# 8-8CONRTOL.net
KiCad netlist of a schematic drawn in Altium Designer
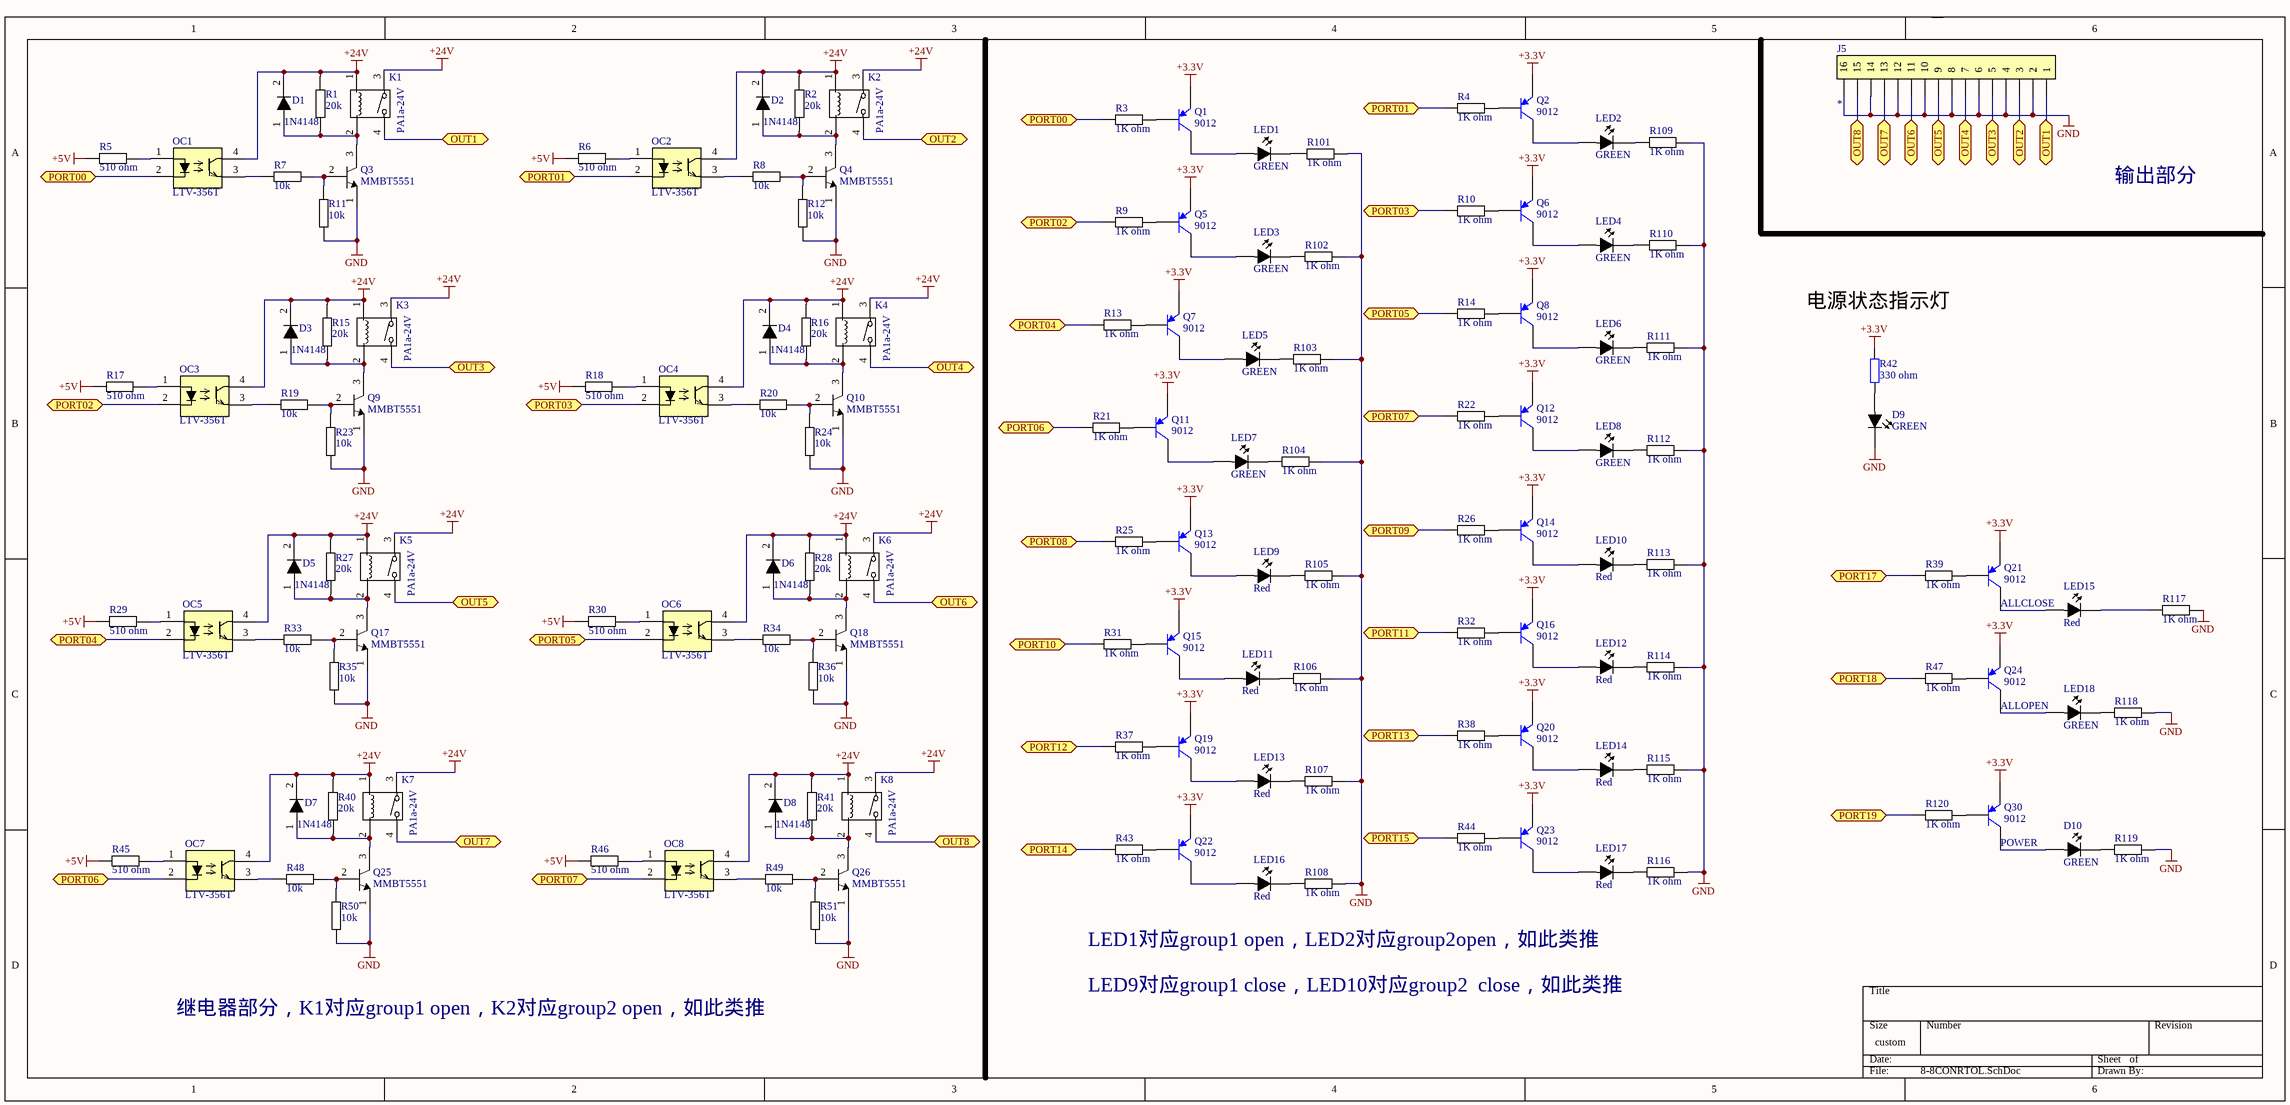
[diagram p0: 8-8CONRTOL.SchDoc]

(export (version "E")
  (design (tool "Eeschema 10.0.6"))
  (components
    (comp (ref "D1")
      (value "1N4148")
      (footprint "D 1N4148(SOD-80/LL-34)")
      (libsource (lib "mylib") (part "Diode"))
    )
    (comp (ref "D2")
      (value "1N4148")
      (footprint "D 1N4148(SOD-80/LL-34)")
      (libsource (lib "mylib") (part "Diode"))
    )
    (comp (ref "D3")
      (value "1N4148")
      (footprint "D 1N4148(SOD-80/LL-34)")
      (libsource (lib "mylib") (part "Diode"))
    )
    (comp (ref "D4")
      (value "1N4148")
      (footprint "D 1N4148(SOD-80/LL-34)")
      (libsource (lib "mylib") (part "Diode"))
    )
    (comp (ref "D5")
      (value "1N4148")
      (footprint "D 1N4148(SOD-80/LL-34)")
      (libsource (lib "mylib") (part "Diode"))
    )
    (comp (ref "D6")
      (value "1N4148")
      (footprint "D 1N4148(SOD-80/LL-34)")
      (libsource (lib "mylib") (part "Diode"))
    )
    (comp (ref "D7")
      (value "1N4148")
      (footprint "D 1N4148(SOD-80/LL-34)")
      (libsource (lib "mylib") (part "Diode"))
    )
    (comp (ref "D8")
      (value "1N4148")
      (footprint "D 1N4148(SOD-80/LL-34)")
      (libsource (lib "mylib") (part "Diode"))
    )
    (comp (ref "D9") (value "GREEN") (footprint "0805 D") (libsource (lib "mylib") (part "LED")))
    (comp (ref "D10") (value "GREEN") (footprint "LED 3mm SIP") (libsource (lib "mylib") (part "LED")))
    (comp (ref "J5")
      (value "Header 1*16")
      (footprint "8-8控制板:TIMECON5.1MMA")
      (fields (field (name "PIN") "*"))
      (libsource (lib "mylib") (part "Header 1*16"))
    )
    (comp (ref "K1") (value "PA1a-24V") (footprint "Relay PA1a-24V") (libsource (lib "mylib") (part "Relay")))
    (comp (ref "K2") (value "PA1a-24V") (footprint "Relay PA1a-24V") (libsource (lib "mylib") (part "Relay")))
    (comp (ref "K3") (value "PA1a-24V") (footprint "Relay PA1a-24V") (libsource (lib "mylib") (part "Relay")))
    (comp (ref "K4") (value "PA1a-24V") (footprint "Relay PA1a-24V") (libsource (lib "mylib") (part "Relay")))
    (comp (ref "K5") (value "PA1a-24V") (footprint "Relay PA1a-24V") (libsource (lib "mylib") (part "Relay")))
    (comp (ref "K6") (value "PA1a-24V") (footprint "Relay PA1a-24V") (libsource (lib "mylib") (part "Relay")))
    (comp (ref "K7") (value "PA1a-24V") (footprint "Relay PA1a-24V") (libsource (lib "mylib") (part "Relay")))
    (comp (ref "K8") (value "PA1a-24V") (footprint "Relay PA1a-24V") (libsource (lib "mylib") (part "Relay")))
    (comp (ref "LED1") (value "GREEN") (footprint "LED 3mm SIP") (libsource (lib "mylib") (part "LED")))
    (comp (ref "LED2") (value "GREEN") (footprint "LED 3mm SIP") (libsource (lib "mylib") (part "LED")))
    (comp (ref "LED3") (value "GREEN") (footprint "LED 3mm SIP") (libsource (lib "mylib") (part "LED")))
    (comp (ref "LED4") (value "GREEN") (footprint "LED 3mm SIP") (libsource (lib "mylib") (part "LED")))
    (comp (ref "LED5") (value "GREEN") (footprint "LED 3mm SIP") (libsource (lib "mylib") (part "LED")))
    (comp (ref "LED6") (value "GREEN") (footprint "LED 3mm SIP") (libsource (lib "mylib") (part "LED")))
    (comp (ref "LED7") (value "GREEN") (footprint "LED 3mm SIP") (libsource (lib "mylib") (part "LED")))
    (comp (ref "LED8") (value "GREEN") (footprint "LED 3mm SIP") (libsource (lib "mylib") (part "LED")))
    (comp (ref "LED9") (value "Red") (footprint "LED 3mm SIP") (libsource (lib "mylib") (part "LED")))
    (comp (ref "LED10") (value "Red") (footprint "LED 3mm SIP") (libsource (lib "mylib") (part "LED")))
    (comp (ref "LED11") (value "Red") (footprint "LED 3mm SIP") (libsource (lib "mylib") (part "LED")))
    (comp (ref "LED12") (value "Red") (footprint "LED 3mm SIP") (libsource (lib "mylib") (part "LED")))
    (comp (ref "LED13") (value "Red") (footprint "LED 3mm SIP") (libsource (lib "mylib") (part "LED")))
    (comp (ref "LED14") (value "Red") (footprint "LED 3mm SIP") (libsource (lib "mylib") (part "LED")))
    (comp (ref "LED15") (value "Red") (footprint "LED 3mm SIP") (libsource (lib "mylib") (part "LED")))
    (comp (ref "LED16") (value "Red") (footprint "LED 3mm SIP") (libsource (lib "mylib") (part "LED")))
    (comp (ref "LED17") (value "Red") (footprint "LED 3mm SIP") (libsource (lib "mylib") (part "LED")))
    (comp (ref "LED18") (value "GREEN") (footprint "LED 3mm SIP") (libsource (lib "mylib") (part "LED")))
    (comp (ref "OC1") (value "LTV-356T") (footprint "SOP-4 LTV356T") (libsource (lib "mylib") (part "Opto1")))
    (comp (ref "OC2") (value "LTV-356T") (footprint "SOP-4 LTV356T") (libsource (lib "mylib") (part "Opto1")))
    (comp (ref "OC3") (value "LTV-356T") (footprint "SOP-4 LTV356T") (libsource (lib "mylib") (part "Opto1")))
    (comp (ref "OC4") (value "LTV-356T") (footprint "SOP-4 LTV356T") (libsource (lib "mylib") (part "Opto1")))
    (comp (ref "OC5") (value "LTV-356T") (footprint "SOP-4 LTV356T") (libsource (lib "mylib") (part "Opto1")))
    (comp (ref "OC6") (value "LTV-356T") (footprint "SOP-4 LTV356T") (libsource (lib "mylib") (part "Opto1")))
    (comp (ref "OC7") (value "LTV-356T") (footprint "SOP-4 LTV356T") (libsource (lib "mylib") (part "Opto1")))
    (comp (ref "OC8") (value "LTV-356T") (footprint "SOP-4 LTV356T") (libsource (lib "mylib") (part "Opto1")))
    (comp (ref "Q1")
      (value "9012")
      (footprint "9012  SOT-23/TO-236)")
      (description "PNP Bipolar Transistor")
      (fields (field (name "PUBLISHER") "Altium Limited"))
      (libsource (lib "Miscellaneous Devices") (part "PNP"))
    )
    (comp (ref "Q2")
      (value "9012")
      (footprint "9012  SOT-23/TO-236)")
      (description "PNP Bipolar Transistor")
      (fields (field (name "PUBLISHER") "Altium Limited"))
      (libsource (lib "Miscellaneous Devices") (part "PNP"))
    )
    (comp (ref "Q3")
      (value "MMBT5551")
      (footprint "MMBT5551(SOT-23/TO-236)")
      (libsource (lib "mylib") (part "NPN"))
    )
    (comp (ref "Q4")
      (value "MMBT5551")
      (footprint "MMBT5551(SOT-23/TO-236)")
      (libsource (lib "mylib") (part "NPN"))
    )
    (comp (ref "Q5")
      (value "9012")
      (footprint "9012  SOT-23/TO-236)")
      (description "PNP Bipolar Transistor")
      (fields (field (name "PUBLISHER") "Altium Limited"))
      (libsource (lib "Miscellaneous Devices") (part "PNP"))
    )
    (comp (ref "Q6")
      (value "9012")
      (footprint "9012  SOT-23/TO-236)")
      (description "PNP Bipolar Transistor")
      (fields (field (name "PUBLISHER") "Altium Limited"))
      (libsource (lib "Miscellaneous Devices") (part "PNP"))
    )
    (comp (ref "Q7")
      (value "9012")
      (footprint "9012  SOT-23/TO-236)")
      (description "PNP Bipolar Transistor")
      (fields (field (name "PUBLISHER") "Altium Limited"))
      (libsource (lib "Miscellaneous Devices") (part "PNP"))
    )
    (comp (ref "Q8")
      (value "9012")
      (footprint "9012  SOT-23/TO-236)")
      (description "PNP Bipolar Transistor")
      (fields (field (name "PUBLISHER") "Altium Limited"))
      (libsource (lib "Miscellaneous Devices") (part "PNP"))
    )
    (comp (ref "Q9")
      (value "MMBT5551")
      (footprint "MMBT5551(SOT-23/TO-236)")
      (libsource (lib "mylib") (part "NPN"))
    )
    (comp (ref "Q10")
      (value "MMBT5551")
      (footprint "MMBT5551(SOT-23/TO-236)")
      (libsource (lib "mylib") (part "NPN"))
    )
    (comp (ref "Q11")
      (value "9012")
      (footprint "9012  SOT-23/TO-236)")
      (description "PNP Bipolar Transistor")
      (fields (field (name "PUBLISHER") "Altium Limited"))
      (libsource (lib "Miscellaneous Devices") (part "PNP"))
    )
    (comp (ref "Q12")
      (value "9012")
      (footprint "9012  SOT-23/TO-236)")
      (description "PNP Bipolar Transistor")
      (fields (field (name "PUBLISHER") "Altium Limited"))
      (libsource (lib "Miscellaneous Devices") (part "PNP"))
    )
    (comp (ref "Q13")
      (value "9012")
      (footprint "9012  SOT-23/TO-236)")
      (description "PNP Bipolar Transistor")
      (fields (field (name "PUBLISHER") "Altium Limited"))
      (libsource (lib "Miscellaneous Devices") (part "PNP"))
    )
    (comp (ref "Q14")
      (value "9012")
      (footprint "9012  SOT-23/TO-236)")
      (description "PNP Bipolar Transistor")
      (fields (field (name "PUBLISHER") "Altium Limited"))
      (libsource (lib "Miscellaneous Devices") (part "PNP"))
    )
    (comp (ref "Q15")
      (value "9012")
      (footprint "9012  SOT-23/TO-236)")
      (description "PNP Bipolar Transistor")
      (fields (field (name "PUBLISHER") "Altium Limited"))
      (libsource (lib "Miscellaneous Devices") (part "PNP"))
    )
    (comp (ref "Q16")
      (value "9012")
      (footprint "9012  SOT-23/TO-236)")
      (description "PNP Bipolar Transistor")
      (fields (field (name "PUBLISHER") "Altium Limited"))
      (libsource (lib "Miscellaneous Devices") (part "PNP"))
    )
    (comp (ref "Q17")
      (value "MMBT5551")
      (footprint "MMBT5551(SOT-23/TO-236)")
      (libsource (lib "mylib") (part "NPN"))
    )
    (comp (ref "Q18")
      (value "MMBT5551")
      (footprint "MMBT5551(SOT-23/TO-236)")
      (libsource (lib "mylib") (part "NPN"))
    )
    (comp (ref "Q19")
      (value "9012")
      (footprint "9012  SOT-23/TO-236)")
      (description "PNP Bipolar Transistor")
      (fields (field (name "PUBLISHER") "Altium Limited"))
      (libsource (lib "Miscellaneous Devices") (part "PNP"))
    )
    (comp (ref "Q20")
      (value "9012")
      (footprint "9012  SOT-23/TO-236)")
      (description "PNP Bipolar Transistor")
      (fields (field (name "PUBLISHER") "Altium Limited"))
      (libsource (lib "Miscellaneous Devices") (part "PNP"))
    )
    (comp (ref "Q21")
      (value "9012")
      (footprint "9012  SOT-23/TO-236)")
      (description "PNP Bipolar Transistor")
      (fields (field (name "PUBLISHER") "Altium Limited"))
      (libsource (lib "Miscellaneous Devices") (part "PNP"))
    )
    (comp (ref "Q22")
      (value "9012")
      (footprint "9012  SOT-23/TO-236)")
      (description "PNP Bipolar Transistor")
      (fields (field (name "PUBLISHER") "Altium Limited"))
      (libsource (lib "Miscellaneous Devices") (part "PNP"))
    )
    (comp (ref "Q23")
      (value "9012")
      (footprint "9012  SOT-23/TO-236)")
      (description "PNP Bipolar Transistor")
      (fields (field (name "PUBLISHER") "Altium Limited"))
      (libsource (lib "Miscellaneous Devices") (part "PNP"))
    )
    (comp (ref "Q24")
      (value "9012")
      (footprint "9012  SOT-23/TO-236)")
      (description "PNP Bipolar Transistor")
      (fields (field (name "PUBLISHER") "Altium Limited"))
      (libsource (lib "Miscellaneous Devices") (part "PNP"))
    )
    (comp (ref "Q25")
      (value "MMBT5551")
      (footprint "MMBT5551(SOT-23/TO-236)")
      (libsource (lib "mylib") (part "NPN"))
    )
    (comp (ref "Q26")
      (value "MMBT5551")
      (footprint "MMBT5551(SOT-23/TO-236)")
      (libsource (lib "mylib") (part "NPN"))
    )
    (comp (ref "Q30")
      (value "9012")
      (footprint "9012  SOT-23/TO-236)")
      (description "PNP Bipolar Transistor")
      (fields (field (name "PUBLISHER") "Altium Limited"))
      (libsource (lib "Miscellaneous Devices") (part "PNP"))
    )
    (comp (ref "R1")
      (value "20k")
      (footprint "0805 R 1/8W")
      (fields (field (name "Comment") "RES"))
      (libsource (lib "") (part "RES_1"))
    )
    (comp (ref "R2")
      (value "20k")
      (footprint "0805 R 1/8W")
      (fields (field (name "Comment") "RES"))
      (libsource (lib "") (part "RES_1"))
    )
    (comp (ref "R3")
      (value "1K ohm")
      (footprint "0805 R 1/8W")
      (fields (field (name "Comment") "RES"))
      (libsource (lib "mylib") (part "RES"))
    )
    (comp (ref "R4")
      (value "1K ohm")
      (footprint "0805 R 1/8W")
      (fields (field (name "Comment") "RES"))
      (libsource (lib "mylib") (part "RES"))
    )
    (comp (ref "R5")
      (value "510 ohm")
      (footprint "0805 R 1/8W")
      (fields (field (name "Comment") "RES"))
      (libsource (lib "mylib") (part "RES"))
    )
    (comp (ref "R6")
      (value "510 ohm")
      (footprint "0805 R 1/8W")
      (fields (field (name "Comment") "RES"))
      (libsource (lib "mylib") (part "RES"))
    )
    (comp (ref "R7")
      (value "10k")
      (footprint "0805 R 1/8W")
      (fields (field (name "Comment") "RES"))
      (libsource (lib "mylib") (part "RES"))
    )
    (comp (ref "R8")
      (value "10k")
      (footprint "0805 R 1/8W")
      (fields (field (name "Comment") "RES"))
      (libsource (lib "mylib") (part "RES"))
    )
    (comp (ref "R9")
      (value "1K ohm")
      (footprint "0805 R 1/8W")
      (fields (field (name "Comment") "RES"))
      (libsource (lib "mylib") (part "RES"))
    )
    (comp (ref "R10")
      (value "1K ohm")
      (footprint "0805 R 1/8W")
      (fields (field (name "Comment") "RES"))
      (libsource (lib "mylib") (part "RES"))
    )
    (comp (ref "R11")
      (value "10k")
      (footprint "0805 R 1/8W")
      (fields (field (name "Comment") "RES"))
      (libsource (lib "") (part "RES_1"))
    )
    (comp (ref "R12")
      (value "10k")
      (footprint "0805 R 1/8W")
      (fields (field (name "Comment") "RES"))
      (libsource (lib "") (part "RES_1"))
    )
    (comp (ref "R13")
      (value "1K ohm")
      (footprint "0805 R 1/8W")
      (fields (field (name "Comment") "RES"))
      (libsource (lib "mylib") (part "RES"))
    )
    (comp (ref "R14")
      (value "1K ohm")
      (footprint "0805 R 1/8W")
      (fields (field (name "Comment") "RES"))
      (libsource (lib "mylib") (part "RES"))
    )
    (comp (ref "R15")
      (value "20k")
      (footprint "0805 R 1/8W")
      (fields (field (name "Comment") "RES"))
      (libsource (lib "") (part "RES_1"))
    )
    (comp (ref "R16")
      (value "20k")
      (footprint "0805 R 1/8W")
      (fields (field (name "Comment") "RES"))
      (libsource (lib "") (part "RES_1"))
    )
    (comp (ref "R17")
      (value "510 ohm")
      (footprint "0805 R 1/8W")
      (fields (field (name "Comment") "RES"))
      (libsource (lib "mylib") (part "RES"))
    )
    (comp (ref "R18")
      (value "510 ohm")
      (footprint "0805 R 1/8W")
      (fields (field (name "Comment") "RES"))
      (libsource (lib "mylib") (part "RES"))
    )
    (comp (ref "R19")
      (value "10k")
      (footprint "0805 R 1/8W")
      (fields (field (name "Comment") "RES"))
      (libsource (lib "mylib") (part "RES"))
    )
    (comp (ref "R20")
      (value "10k")
      (footprint "0805 R 1/8W")
      (fields (field (name "Comment") "RES"))
      (libsource (lib "mylib") (part "RES"))
    )
    (comp (ref "R21")
      (value "1K ohm")
      (footprint "0805 R 1/8W")
      (fields (field (name "Comment") "RES"))
      (libsource (lib "mylib") (part "RES"))
    )
    (comp (ref "R22")
      (value "1K ohm")
      (footprint "0805 R 1/8W")
      (fields (field (name "Comment") "RES"))
      (libsource (lib "mylib") (part "RES"))
    )
    (comp (ref "R23")
      (value "10k")
      (footprint "0805 R 1/8W")
      (fields (field (name "Comment") "RES"))
      (libsource (lib "") (part "RES_1"))
    )
    (comp (ref "R24")
      (value "10k")
      (footprint "0805 R 1/8W")
      (fields (field (name "Comment") "RES"))
      (libsource (lib "") (part "RES_1"))
    )
    (comp (ref "R25")
      (value "1K ohm")
      (footprint "0805 R 1/8W")
      (fields (field (name "Comment") "RES"))
      (libsource (lib "mylib") (part "RES"))
    )
    (comp (ref "R26")
      (value "1K ohm")
      (footprint "0805 R 1/8W")
      (fields (field (name "Comment") "RES"))
      (libsource (lib "mylib") (part "RES"))
    )
    (comp (ref "R27")
      (value "20k")
      (footprint "0805 R 1/8W")
      (fields (field (name "Comment") "RES"))
      (libsource (lib "") (part "RES_1"))
    )
    (comp (ref "R28")
      (value "20k")
      (footprint "0805 R 1/8W")
      (fields (field (name "Comment") "RES"))
      (libsource (lib "") (part "RES_1"))
    )
    (comp (ref "R29")
      (value "510 ohm")
      (footprint "0805 R 1/8W")
      (fields (field (name "Comment") "RES"))
      (libsource (lib "mylib") (part "RES"))
    )
    (comp (ref "R30")
      (value "510 ohm")
      (footprint "0805 R 1/8W")
      (fields (field (name "Comment") "RES"))
      (libsource (lib "mylib") (part "RES"))
    )
    (comp (ref "R31")
      (value "1K ohm")
      (footprint "0805 R 1/8W")
      (fields (field (name "Comment") "RES"))
      (libsource (lib "mylib") (part "RES"))
    )
    (comp (ref "R32")
      (value "1K ohm")
      (footprint "0805 R 1/8W")
      (fields (field (name "Comment") "RES"))
      (libsource (lib "mylib") (part "RES"))
    )
    (comp (ref "R33")
      (value "10k")
      (footprint "0805 R 1/8W")
      (fields (field (name "Comment") "RES"))
      (libsource (lib "mylib") (part "RES"))
    )
    (comp (ref "R34")
      (value "10k")
      (footprint "0805 R 1/8W")
      (fields (field (name "Comment") "RES"))
      (libsource (lib "mylib") (part "RES"))
    )
    (comp (ref "R35")
      (value "10k")
      (footprint "0805 R 1/8W")
      (fields (field (name "Comment") "RES"))
      (libsource (lib "") (part "RES_1"))
    )
    (comp (ref "R36")
      (value "10k")
      (footprint "0805 R 1/8W")
      (fields (field (name "Comment") "RES"))
      (libsource (lib "") (part "RES_1"))
    )
    (comp (ref "R37")
      (value "1K ohm")
      (footprint "0805 R 1/8W")
      (fields (field (name "Comment") "RES"))
      (libsource (lib "mylib") (part "RES"))
    )
    (comp (ref "R38")
      (value "1K ohm")
      (footprint "0805 R 1/8W")
      (fields (field (name "Comment") "RES"))
      (libsource (lib "mylib") (part "RES"))
    )
    (comp (ref "R39")
      (value "1K ohm")
      (footprint "0805 R 1/8W")
      (fields (field (name "Comment") "RES"))
      (libsource (lib "mylib") (part "RES"))
    )
    (comp (ref "R40")
      (value "20k")
      (footprint "0805 R 1/8W")
      (fields (field (name "Comment") "RES"))
      (libsource (lib "") (part "RES_1"))
    )
    (comp (ref "R41")
      (value "20k")
      (footprint "0805 R 1/8W")
      (fields (field (name "Comment") "RES"))
      (libsource (lib "") (part "RES_1"))
    )
    (comp (ref "R42")
      (value "330 ohm")
      (footprint "0805 D")
      (description "Resistor")
      (fields (field (name "PUBLISHER") "Altium Limited"))
      (libsource (lib "ABIDO") (part "Res2"))
    )
    (comp (ref "R43")
      (value "1K ohm")
      (footprint "0805 R 1/8W")
      (fields (field (name "Comment") "RES"))
      (libsource (lib "mylib") (part "RES"))
    )
    (comp (ref "R44")
      (value "1K ohm")
      (footprint "0805 R 1/8W")
      (fields (field (name "Comment") "RES"))
      (libsource (lib "mylib") (part "RES"))
    )
    (comp (ref "R45")
      (value "510 ohm")
      (footprint "0805 R 1/8W")
      (fields (field (name "Comment") "RES"))
      (libsource (lib "mylib") (part "RES"))
    )
    (comp (ref "R46")
      (value "510 ohm")
      (footprint "0805 R 1/8W")
      (fields (field (name "Comment") "RES"))
      (libsource (lib "mylib") (part "RES"))
    )
    (comp (ref "R47")
      (value "1K ohm")
      (footprint "0805 R 1/8W")
      (fields (field (name "Comment") "RES"))
      (libsource (lib "mylib") (part "RES"))
    )
    (comp (ref "R48")
      (value "10k")
      (footprint "0805 R 1/8W")
      (fields (field (name "Comment") "RES"))
      (libsource (lib "mylib") (part "RES"))
    )
    (comp (ref "R49")
      (value "10k")
      (footprint "0805 R 1/8W")
      (fields (field (name "Comment") "RES"))
      (libsource (lib "mylib") (part "RES"))
    )
    (comp (ref "R50")
      (value "10k")
      (footprint "0805 R 1/8W")
      (fields (field (name "Comment") "RES"))
      (libsource (lib "") (part "RES_1"))
    )
    (comp (ref "R51")
      (value "10k")
      (footprint "0805 R 1/8W")
      (fields (field (name "Comment") "RES"))
      (libsource (lib "") (part "RES_1"))
    )
    (comp (ref "R101")
      (value "1K ohm")
      (footprint "0805 R 1/8W")
      (fields (field (name "Comment") "RES"))
      (libsource (lib "mylib") (part "RES"))
    )
    (comp (ref "R102")
      (value "1K ohm")
      (footprint "0805 R 1/8W")
      (fields (field (name "Comment") "RES"))
      (libsource (lib "mylib") (part "RES"))
    )
    (comp (ref "R103")
      (value "1K ohm")
      (footprint "0805 R 1/8W")
      (fields (field (name "Comment") "RES"))
      (libsource (lib "mylib") (part "RES"))
    )
    (comp (ref "R104")
      (value "1K ohm")
      (footprint "0805 R 1/8W")
      (fields (field (name "Comment") "RES"))
      (libsource (lib "mylib") (part "RES"))
    )
    (comp (ref "R105")
      (value "1K ohm")
      (footprint "0805 R 1/8W")
      (fields (field (name "Comment") "RES"))
      (libsource (lib "mylib") (part "RES"))
    )
    (comp (ref "R106")
      (value "1K ohm")
      (footprint "0805 R 1/8W")
      (fields (field (name "Comment") "RES"))
      (libsource (lib "mylib") (part "RES"))
    )
    (comp (ref "R107")
      (value "1K ohm")
      (footprint "0805 R 1/8W")
      (fields (field (name "Comment") "RES"))
      (libsource (lib "mylib") (part "RES"))
    )
    (comp (ref "R108")
      (value "1K ohm")
      (footprint "0805 R 1/8W")
      (fields (field (name "Comment") "RES"))
      (libsource (lib "mylib") (part "RES"))
    )
    (comp (ref "R109")
      (value "1K ohm")
      (footprint "0805 R 1/8W")
      (fields (field (name "Comment") "RES"))
      (libsource (lib "mylib") (part "RES"))
    )
    (comp (ref "R110")
      (value "1K ohm")
      (footprint "0805 R 1/8W")
      (fields (field (name "Comment") "RES"))
      (libsource (lib "mylib") (part "RES"))
    )
    (comp (ref "R111")
      (value "1K ohm")
      (footprint "0805 R 1/8W")
      (fields (field (name "Comment") "RES"))
      (libsource (lib "mylib") (part "RES"))
    )
    (comp (ref "R112")
      (value "1K ohm")
      (footprint "0805 R 1/8W")
      (fields (field (name "Comment") "RES"))
      (libsource (lib "mylib") (part "RES"))
    )
    (comp (ref "R113")
      (value "1K ohm")
      (footprint "0805 R 1/8W")
      (fields (field (name "Comment") "RES"))
      (libsource (lib "mylib") (part "RES"))
    )
    (comp (ref "R114")
      (value "1K ohm")
      (footprint "0805 R 1/8W")
      (fields (field (name "Comment") "RES"))
      (libsource (lib "mylib") (part "RES"))
    )
    (comp (ref "R115")
      (value "1K ohm")
      (footprint "0805 R 1/8W")
      (fields (field (name "Comment") "RES"))
      (libsource (lib "mylib") (part "RES"))
    )
    (comp (ref "R116")
      (value "1K ohm")
      (footprint "0805 R 1/8W")
      (fields (field (name "Comment") "RES"))
      (libsource (lib "mylib") (part "RES"))
    )
    (comp (ref "R117")
      (value "1K ohm")
      (footprint "0805 R 1/8W")
      (fields (field (name "Comment") "RES"))
      (libsource (lib "mylib") (part "RES"))
    )
    (comp (ref "R118")
      (value "1K ohm")
      (footprint "0805 R 1/8W")
      (fields (field (name "Comment") "RES"))
      (libsource (lib "mylib") (part "RES"))
    )
    (comp (ref "R119")
      (value "1K ohm")
      (footprint "0805 R 1/8W")
      (fields (field (name "Comment") "RES"))
      (libsource (lib "mylib") (part "RES"))
    )
    (comp (ref "R120")
      (value "1K ohm")
      (footprint "0805 R 1/8W")
      (fields (field (name "Comment") "RES"))
      (libsource (lib "mylib") (part "RES"))
    )
  )
  (nets
    (net (code "1") (name "+3.3V") (class "Default")
      (node (ref "Q1") (pin "2") (pinfunction "E_2") (pintype "passive"))
      (node (ref "Q11") (pin "2") (pinfunction "E_2") (pintype "passive"))
      (node (ref "Q12") (pin "2") (pinfunction "E_2") (pintype "passive"))
      (node (ref "Q13") (pin "2") (pinfunction "E_2") (pintype "passive"))
      (node (ref "Q14") (pin "2") (pinfunction "E_2") (pintype "passive"))
      (node (ref "Q15") (pin "2") (pinfunction "E_2") (pintype "passive"))
      (node (ref "Q16") (pin "2") (pinfunction "E_2") (pintype "passive"))
      (node (ref "Q19") (pin "2") (pinfunction "E_2") (pintype "passive"))
      (node (ref "Q2") (pin "2") (pinfunction "E_2") (pintype "passive"))
      (node (ref "Q20") (pin "2") (pinfunction "E_2") (pintype "passive"))
      (node (ref "Q21") (pin "2") (pinfunction "E_2") (pintype "passive"))
      (node (ref "Q22") (pin "2") (pinfunction "E_2") (pintype "passive"))
      (node (ref "Q23") (pin "2") (pinfunction "E_2") (pintype "passive"))
      (node (ref "Q24") (pin "2") (pinfunction "E_2") (pintype "passive"))
      (node (ref "Q30") (pin "2") (pinfunction "E_2") (pintype "passive"))
      (node (ref "Q5") (pin "2") (pinfunction "E_2") (pintype "passive"))
      (node (ref "Q6") (pin "2") (pinfunction "E_2") (pintype "passive"))
      (node (ref "Q7") (pin "2") (pinfunction "E_2") (pintype "passive"))
      (node (ref "Q8") (pin "2") (pinfunction "E_2") (pintype "passive"))
      (node (ref "R42") (pin "2") (pinfunction "2_2") (pintype "passive"))
    )
    (net (code "2") (name "+5V") (class "Default")
      (node (ref "R17") (pin "1") (pinfunction "1_1") (pintype "passive"))
      (node (ref "R18") (pin "1") (pinfunction "1_1") (pintype "passive"))
      (node (ref "R29") (pin "1") (pinfunction "1_1") (pintype "passive"))
      (node (ref "R30") (pin "1") (pinfunction "1_1") (pintype "passive"))
      (node (ref "R45") (pin "1") (pinfunction "1_1") (pintype "passive"))
      (node (ref "R46") (pin "1") (pinfunction "1_1") (pintype "passive"))
      (node (ref "R5") (pin "1") (pinfunction "1_1") (pintype "passive"))
      (node (ref "R6") (pin "1") (pinfunction "1_1") (pintype "passive"))
    )
    (net (code "3") (name "+24V") (class "Default")
      (node (ref "D1") (pin "2") (pinfunction "K_2") (pintype "passive"))
      (node (ref "D2") (pin "2") (pinfunction "K_2") (pintype "passive"))
      (node (ref "D3") (pin "2") (pinfunction "K_2") (pintype "passive"))
      (node (ref "D4") (pin "2") (pinfunction "K_2") (pintype "passive"))
      (node (ref "D5") (pin "2") (pinfunction "K_2") (pintype "passive"))
      (node (ref "D6") (pin "2") (pinfunction "K_2") (pintype "passive"))
      (node (ref "D7") (pin "2") (pinfunction "K_2") (pintype "passive"))
      (node (ref "D8") (pin "2") (pinfunction "K_2") (pintype "passive"))
      (node (ref "K1") (pin "1") (pinfunction "1_1") (pintype "passive"))
      (node (ref "K1") (pin "3") (pinfunction "3_3") (pintype "passive"))
      (node (ref "K2") (pin "1") (pinfunction "1_1") (pintype "passive"))
      (node (ref "K2") (pin "3") (pinfunction "3_3") (pintype "passive"))
      (node (ref "K3") (pin "1") (pinfunction "1_1") (pintype "passive"))
      (node (ref "K3") (pin "3") (pinfunction "3_3") (pintype "passive"))
      (node (ref "K4") (pin "1") (pinfunction "1_1") (pintype "passive"))
      (node (ref "K4") (pin "3") (pinfunction "3_3") (pintype "passive"))
      (node (ref "K5") (pin "1") (pinfunction "1_1") (pintype "passive"))
      (node (ref "K5") (pin "3") (pinfunction "3_3") (pintype "passive"))
      (node (ref "K6") (pin "1") (pinfunction "1_1") (pintype "passive"))
      (node (ref "K6") (pin "3") (pinfunction "3_3") (pintype "passive"))
      (node (ref "K7") (pin "1") (pinfunction "1_1") (pintype "passive"))
      (node (ref "K7") (pin "3") (pinfunction "3_3") (pintype "passive"))
      (node (ref "K8") (pin "1") (pinfunction "1_1") (pintype "passive"))
      (node (ref "K8") (pin "3") (pinfunction "3_3") (pintype "passive"))
      (node (ref "OC1") (pin "4") (pintype "passive"))
      (node (ref "OC2") (pin "4") (pintype "passive"))
      (node (ref "OC3") (pin "4") (pintype "passive"))
      (node (ref "OC4") (pin "4") (pintype "passive"))
      (node (ref "OC5") (pin "4") (pintype "passive"))
      (node (ref "OC6") (pin "4") (pintype "passive"))
      (node (ref "OC7") (pin "4") (pintype "passive"))
      (node (ref "OC8") (pin "4") (pintype "passive"))
      (node (ref "R1") (pin "2") (pinfunction "2_2") (pintype "passive"))
      (node (ref "R15") (pin "2") (pinfunction "2_2") (pintype "passive"))
      (node (ref "R16") (pin "2") (pinfunction "2_2") (pintype "passive"))
      (node (ref "R2") (pin "2") (pinfunction "2_2") (pintype "passive"))
      (node (ref "R27") (pin "2") (pinfunction "2_2") (pintype "passive"))
      (node (ref "R28") (pin "2") (pinfunction "2_2") (pintype "passive"))
      (node (ref "R40") (pin "2") (pinfunction "2_2") (pintype "passive"))
      (node (ref "R41") (pin "2") (pinfunction "2_2") (pintype "passive"))
    )
    (net (code "4") (name "/OUT1") (class "Default")
      (node (ref "J5") (pin "1") (pinfunction "1_1") (pintype "passive"))
      (node (ref "K1") (pin "4") (pinfunction "4_4") (pintype "passive"))
    )
    (net (code "5") (name "/OUT2") (class "Default")
      (node (ref "J5") (pin "3") (pinfunction "3_3") (pintype "passive"))
      (node (ref "K2") (pin "4") (pinfunction "4_4") (pintype "passive"))
    )
    (net (code "6") (name "/OUT3") (class "Default")
      (node (ref "J5") (pin "5") (pinfunction "5_5") (pintype "passive"))
      (node (ref "K3") (pin "4") (pinfunction "4_4") (pintype "passive"))
    )
    (net (code "7") (name "/OUT4") (class "Default")
      (node (ref "J5") (pin "7") (pinfunction "7_7") (pintype "passive"))
      (node (ref "K4") (pin "4") (pinfunction "4_4") (pintype "passive"))
    )
    (net (code "8") (name "/OUT5") (class "Default")
      (node (ref "J5") (pin "9") (pinfunction "9_9") (pintype "passive"))
      (node (ref "K5") (pin "4") (pinfunction "4_4") (pintype "passive"))
    )
    (net (code "9") (name "/OUT6") (class "Default")
      (node (ref "J5") (pin "11") (pinfunction "11_11") (pintype "passive"))
      (node (ref "K6") (pin "4") (pinfunction "4_4") (pintype "passive"))
    )
    (net (code "10") (name "/OUT7") (class "Default")
      (node (ref "J5") (pin "13") (pinfunction "13_13") (pintype "passive"))
      (node (ref "K7") (pin "4") (pinfunction "4_4") (pintype "passive"))
    )
    (net (code "11") (name "/OUT8") (class "Default")
      (node (ref "J5") (pin "15") (pinfunction "15_15") (pintype "passive"))
      (node (ref "K8") (pin "4") (pinfunction "4_4") (pintype "passive"))
    )
    (net (code "12") (name "/PORT00") (class "Default")
      (node (ref "OC1") (pin "2") (pintype "passive"))
      (node (ref "R3") (pin "1") (pinfunction "1_1") (pintype "passive"))
    )
    (net (code "13") (name "/PORT01") (class "Default")
      (node (ref "OC2") (pin "2") (pintype "passive"))
      (node (ref "R4") (pin "1") (pinfunction "1_1") (pintype "passive"))
    )
    (net (code "14") (name "/PORT02") (class "Default")
      (node (ref "OC3") (pin "2") (pintype "passive"))
      (node (ref "R9") (pin "1") (pinfunction "1_1") (pintype "passive"))
    )
    (net (code "15") (name "/PORT03") (class "Default")
      (node (ref "OC4") (pin "2") (pintype "passive"))
      (node (ref "R10") (pin "1") (pinfunction "1_1") (pintype "passive"))
    )
    (net (code "16") (name "/PORT04") (class "Default")
      (node (ref "OC5") (pin "2") (pintype "passive"))
      (node (ref "R13") (pin "1") (pinfunction "1_1") (pintype "passive"))
    )
    (net (code "17") (name "/PORT05") (class "Default")
      (node (ref "OC6") (pin "2") (pintype "passive"))
      (node (ref "R14") (pin "1") (pinfunction "1_1") (pintype "passive"))
    )
    (net (code "18") (name "/PORT06") (class "Default")
      (node (ref "OC7") (pin "2") (pintype "passive"))
      (node (ref "R21") (pin "1") (pinfunction "1_1") (pintype "passive"))
    )
    (net (code "19") (name "/PORT07") (class "Default")
      (node (ref "OC8") (pin "2") (pintype "passive"))
      (node (ref "R22") (pin "1") (pinfunction "1_1") (pintype "passive"))
    )
    (net (code "20") (name "/PORT08") (class "Default")
      (node (ref "R25") (pin "1") (pinfunction "1_1") (pintype "passive"))
    )
    (net (code "21") (name "/PORT09") (class "Default")
      (node (ref "R26") (pin "1") (pinfunction "1_1") (pintype "passive"))
    )
    (net (code "22") (name "/PORT10") (class "Default")
      (node (ref "R31") (pin "1") (pinfunction "1_1") (pintype "passive"))
    )
    (net (code "23") (name "/PORT11") (class "Default")
      (node (ref "R32") (pin "1") (pinfunction "1_1") (pintype "passive"))
    )
    (net (code "24") (name "/PORT12") (class "Default")
      (node (ref "R37") (pin "1") (pinfunction "1_1") (pintype "passive"))
    )
    (net (code "25") (name "/PORT13") (class "Default")
      (node (ref "R38") (pin "1") (pinfunction "1_1") (pintype "passive"))
    )
    (net (code "26") (name "/PORT14") (class "Default")
      (node (ref "R43") (pin "1") (pinfunction "1_1") (pintype "passive"))
    )
    (net (code "27") (name "/PORT15") (class "Default")
      (node (ref "R44") (pin "1") (pinfunction "1_1") (pintype "passive"))
    )
    (net (code "28") (name "/PORT17") (class "Default")
      (node (ref "R39") (pin "1") (pinfunction "1_1") (pintype "passive"))
    )
    (net (code "29") (name "/PORT18") (class "Default")
      (node (ref "R47") (pin "1") (pinfunction "1_1") (pintype "passive"))
    )
    (net (code "30") (name "/PORT19") (class "Default")
      (node (ref "R120") (pin "1") (pinfunction "1_1") (pintype "passive"))
    )
    (net (code "31") (name "GND") (class "Default")
      (node (ref "D9") (pin "2") (pinfunction "K_2") (pintype "passive"))
      (node (ref "J5") (pin "10") (pinfunction "10_10") (pintype "passive"))
      (node (ref "J5") (pin "12") (pinfunction "12_12") (pintype "passive"))
      (node (ref "J5") (pin "14") (pinfunction "14_14") (pintype "passive"))
      (node (ref "J5") (pin "16") (pinfunction "16_16") (pintype "passive"))
      (node (ref "J5") (pin "2") (pinfunction "2_2") (pintype "passive"))
      (node (ref "J5") (pin "4") (pinfunction "4_4") (pintype "passive"))
      (node (ref "J5") (pin "6") (pinfunction "6_6") (pintype "passive"))
      (node (ref "J5") (pin "8") (pinfunction "8_8") (pintype "passive"))
      (node (ref "Q10") (pin "1") (pinfunction "E_1") (pintype "passive"))
      (node (ref "Q17") (pin "1") (pinfunction "E_1") (pintype "passive"))
      (node (ref "Q18") (pin "1") (pinfunction "E_1") (pintype "passive"))
      (node (ref "Q25") (pin "1") (pinfunction "E_1") (pintype "passive"))
      (node (ref "Q26") (pin "1") (pinfunction "E_1") (pintype "passive"))
      (node (ref "Q3") (pin "1") (pinfunction "E_1") (pintype "passive"))
      (node (ref "Q4") (pin "1") (pinfunction "E_1") (pintype "passive"))
      (node (ref "Q9") (pin "1") (pinfunction "E_1") (pintype "passive"))
      (node (ref "R101") (pin "2") (pinfunction "2_2") (pintype "passive"))
      (node (ref "R102") (pin "2") (pinfunction "2_2") (pintype "passive"))
      (node (ref "R103") (pin "2") (pinfunction "2_2") (pintype "passive"))
      (node (ref "R104") (pin "2") (pinfunction "2_2") (pintype "passive"))
      (node (ref "R105") (pin "2") (pinfunction "2_2") (pintype "passive"))
      (node (ref "R106") (pin "2") (pinfunction "2_2") (pintype "passive"))
      (node (ref "R107") (pin "2") (pinfunction "2_2") (pintype "passive"))
      (node (ref "R108") (pin "2") (pinfunction "2_2") (pintype "passive"))
      (node (ref "R109") (pin "2") (pinfunction "2_2") (pintype "passive"))
      (node (ref "R11") (pin "1") (pinfunction "1_1") (pintype "passive"))
      (node (ref "R110") (pin "2") (pinfunction "2_2") (pintype "passive"))
      (node (ref "R111") (pin "2") (pinfunction "2_2") (pintype "passive"))
      (node (ref "R112") (pin "2") (pinfunction "2_2") (pintype "passive"))
      (node (ref "R113") (pin "2") (pinfunction "2_2") (pintype "passive"))
      (node (ref "R114") (pin "2") (pinfunction "2_2") (pintype "passive"))
      (node (ref "R115") (pin "2") (pinfunction "2_2") (pintype "passive"))
      (node (ref "R116") (pin "2") (pinfunction "2_2") (pintype "passive"))
      (node (ref "R117") (pin "2") (pinfunction "2_2") (pintype "passive"))
      (node (ref "R118") (pin "2") (pinfunction "2_2") (pintype "passive"))
      (node (ref "R119") (pin "2") (pinfunction "2_2") (pintype "passive"))
      (node (ref "R12") (pin "1") (pinfunction "1_1") (pintype "passive"))
      (node (ref "R23") (pin "1") (pinfunction "1_1") (pintype "passive"))
      (node (ref "R24") (pin "1") (pinfunction "1_1") (pintype "passive"))
      (node (ref "R35") (pin "1") (pinfunction "1_1") (pintype "passive"))
      (node (ref "R36") (pin "1") (pinfunction "1_1") (pintype "passive"))
      (node (ref "R50") (pin "1") (pinfunction "1_1") (pintype "passive"))
      (node (ref "R51") (pin "1") (pinfunction "1_1") (pintype "passive"))
    )
    (net (code "32") (name "Net-(D1-A)") (class "Default")
      (node (ref "D1") (pin "1") (pinfunction "A_1") (pintype "passive"))
      (node (ref "K1") (pin "2") (pinfunction "2_2") (pintype "passive"))
      (node (ref "Q3") (pin "3") (pinfunction "C_3") (pintype "passive"))
      (node (ref "R1") (pin "1") (pinfunction "1_1") (pintype "passive"))
    )
    (net (code "33") (name "Net-(D2-A)") (class "Default")
      (node (ref "D2") (pin "1") (pinfunction "A_1") (pintype "passive"))
      (node (ref "K2") (pin "2") (pinfunction "2_2") (pintype "passive"))
      (node (ref "Q4") (pin "3") (pinfunction "C_3") (pintype "passive"))
      (node (ref "R2") (pin "1") (pinfunction "1_1") (pintype "passive"))
    )
    (net (code "34") (name "Net-(D3-A)") (class "Default")
      (node (ref "D3") (pin "1") (pinfunction "A_1") (pintype "passive"))
      (node (ref "K3") (pin "2") (pinfunction "2_2") (pintype "passive"))
      (node (ref "Q9") (pin "3") (pinfunction "C_3") (pintype "passive"))
      (node (ref "R15") (pin "1") (pinfunction "1_1") (pintype "passive"))
    )
    (net (code "35") (name "Net-(D4-A)") (class "Default")
      (node (ref "D4") (pin "1") (pinfunction "A_1") (pintype "passive"))
      (node (ref "K4") (pin "2") (pinfunction "2_2") (pintype "passive"))
      (node (ref "Q10") (pin "3") (pinfunction "C_3") (pintype "passive"))
      (node (ref "R16") (pin "1") (pinfunction "1_1") (pintype "passive"))
    )
    (net (code "36") (name "Net-(D5-A)") (class "Default")
      (node (ref "D5") (pin "1") (pinfunction "A_1") (pintype "passive"))
      (node (ref "K5") (pin "2") (pinfunction "2_2") (pintype "passive"))
      (node (ref "Q17") (pin "3") (pinfunction "C_3") (pintype "passive"))
      (node (ref "R27") (pin "1") (pinfunction "1_1") (pintype "passive"))
    )
    (net (code "37") (name "Net-(D6-A)") (class "Default")
      (node (ref "D6") (pin "1") (pinfunction "A_1") (pintype "passive"))
      (node (ref "K6") (pin "2") (pinfunction "2_2") (pintype "passive"))
      (node (ref "Q18") (pin "3") (pinfunction "C_3") (pintype "passive"))
      (node (ref "R28") (pin "1") (pinfunction "1_1") (pintype "passive"))
    )
    (net (code "38") (name "Net-(D7-A)") (class "Default")
      (node (ref "D7") (pin "1") (pinfunction "A_1") (pintype "passive"))
      (node (ref "K7") (pin "2") (pinfunction "2_2") (pintype "passive"))
      (node (ref "Q25") (pin "3") (pinfunction "C_3") (pintype "passive"))
      (node (ref "R40") (pin "1") (pinfunction "1_1") (pintype "passive"))
    )
    (net (code "39") (name "Net-(D8-A)") (class "Default")
      (node (ref "D8") (pin "1") (pinfunction "A_1") (pintype "passive"))
      (node (ref "K8") (pin "2") (pinfunction "2_2") (pintype "passive"))
      (node (ref "Q26") (pin "3") (pinfunction "C_3") (pintype "passive"))
      (node (ref "R41") (pin "1") (pinfunction "1_1") (pintype "passive"))
    )
    (net (code "40") (name "Net-(D9-A)") (class "Default")
      (node (ref "D9") (pin "1") (pinfunction "A_1") (pintype "passive"))
      (node (ref "R42") (pin "1") (pinfunction "1_1") (pintype "passive"))
    )
    (net (code "41") (name "Net-(D10-A)") (class "Default")
      (node (ref "D10") (pin "1") (pinfunction "A_1") (pintype "passive"))
      (node (ref "Q30") (pin "3") (pinfunction "C_3") (pintype "passive"))
    )
    (net (code "42") (name "Net-(D10-K)") (class "Default")
      (node (ref "D10") (pin "2") (pinfunction "K_2") (pintype "passive"))
      (node (ref "R119") (pin "1") (pinfunction "1_1") (pintype "passive"))
    )
    (net (code "43") (name "Net-(LED1-A)") (class "Default")
      (node (ref "LED1") (pin "1") (pinfunction "A_1") (pintype "passive"))
      (node (ref "Q1") (pin "3") (pinfunction "C_3") (pintype "passive"))
    )
    (net (code "44") (name "Net-(LED1-K)") (class "Default")
      (node (ref "LED1") (pin "2") (pinfunction "K_2") (pintype "passive"))
      (node (ref "R101") (pin "1") (pinfunction "1_1") (pintype "passive"))
    )
    (net (code "45") (name "Net-(LED2-A)") (class "Default")
      (node (ref "LED2") (pin "1") (pinfunction "A_1") (pintype "passive"))
      (node (ref "Q2") (pin "3") (pinfunction "C_3") (pintype "passive"))
    )
    (net (code "46") (name "Net-(LED2-K)") (class "Default")
      (node (ref "LED2") (pin "2") (pinfunction "K_2") (pintype "passive"))
      (node (ref "R109") (pin "1") (pinfunction "1_1") (pintype "passive"))
    )
    (net (code "47") (name "Net-(LED3-A)") (class "Default")
      (node (ref "LED3") (pin "1") (pinfunction "A_1") (pintype "passive"))
      (node (ref "Q5") (pin "3") (pinfunction "C_3") (pintype "passive"))
    )
    (net (code "48") (name "Net-(LED3-K)") (class "Default")
      (node (ref "LED3") (pin "2") (pinfunction "K_2") (pintype "passive"))
      (node (ref "R102") (pin "1") (pinfunction "1_1") (pintype "passive"))
    )
    (net (code "49") (name "Net-(LED4-A)") (class "Default")
      (node (ref "LED4") (pin "1") (pinfunction "A_1") (pintype "passive"))
      (node (ref "Q6") (pin "3") (pinfunction "C_3") (pintype "passive"))
    )
    (net (code "50") (name "Net-(LED4-K)") (class "Default")
      (node (ref "LED4") (pin "2") (pinfunction "K_2") (pintype "passive"))
      (node (ref "R110") (pin "1") (pinfunction "1_1") (pintype "passive"))
    )
    (net (code "51") (name "Net-(LED5-A)") (class "Default")
      (node (ref "LED5") (pin "1") (pinfunction "A_1") (pintype "passive"))
      (node (ref "Q7") (pin "3") (pinfunction "C_3") (pintype "passive"))
    )
    (net (code "52") (name "Net-(LED5-K)") (class "Default")
      (node (ref "LED5") (pin "2") (pinfunction "K_2") (pintype "passive"))
      (node (ref "R103") (pin "1") (pinfunction "1_1") (pintype "passive"))
    )
    (net (code "53") (name "Net-(LED6-A)") (class "Default")
      (node (ref "LED6") (pin "1") (pinfunction "A_1") (pintype "passive"))
      (node (ref "Q8") (pin "3") (pinfunction "C_3") (pintype "passive"))
    )
    (net (code "54") (name "Net-(LED6-K)") (class "Default")
      (node (ref "LED6") (pin "2") (pinfunction "K_2") (pintype "passive"))
      (node (ref "R111") (pin "1") (pinfunction "1_1") (pintype "passive"))
    )
    (net (code "55") (name "Net-(LED7-A)") (class "Default")
      (node (ref "LED7") (pin "1") (pinfunction "A_1") (pintype "passive"))
      (node (ref "Q11") (pin "3") (pinfunction "C_3") (pintype "passive"))
    )
    (net (code "56") (name "Net-(LED7-K)") (class "Default")
      (node (ref "LED7") (pin "2") (pinfunction "K_2") (pintype "passive"))
      (node (ref "R104") (pin "1") (pinfunction "1_1") (pintype "passive"))
    )
    (net (code "57") (name "Net-(LED8-A)") (class "Default")
      (node (ref "LED8") (pin "1") (pinfunction "A_1") (pintype "passive"))
      (node (ref "Q12") (pin "3") (pinfunction "C_3") (pintype "passive"))
    )
    (net (code "58") (name "Net-(LED8-K)") (class "Default")
      (node (ref "LED8") (pin "2") (pinfunction "K_2") (pintype "passive"))
      (node (ref "R112") (pin "1") (pinfunction "1_1") (pintype "passive"))
    )
    (net (code "59") (name "Net-(LED9-A)") (class "Default")
      (node (ref "LED9") (pin "1") (pinfunction "A_1") (pintype "passive"))
      (node (ref "Q13") (pin "3") (pinfunction "C_3") (pintype "passive"))
    )
    (net (code "60") (name "Net-(LED9-K)") (class "Default")
      (node (ref "LED9") (pin "2") (pinfunction "K_2") (pintype "passive"))
      (node (ref "R105") (pin "1") (pinfunction "1_1") (pintype "passive"))
    )
    (net (code "61") (name "Net-(LED10-A)") (class "Default")
      (node (ref "LED10") (pin "1") (pinfunction "A_1") (pintype "passive"))
      (node (ref "Q14") (pin "3") (pinfunction "C_3") (pintype "passive"))
    )
    (net (code "62") (name "Net-(LED10-K)") (class "Default")
      (node (ref "LED10") (pin "2") (pinfunction "K_2") (pintype "passive"))
      (node (ref "R113") (pin "1") (pinfunction "1_1") (pintype "passive"))
    )
    (net (code "63") (name "Net-(LED11-A)") (class "Default")
      (node (ref "LED11") (pin "1") (pinfunction "A_1") (pintype "passive"))
      (node (ref "Q15") (pin "3") (pinfunction "C_3") (pintype "passive"))
    )
    (net (code "64") (name "Net-(LED11-K)") (class "Default")
      (node (ref "LED11") (pin "2") (pinfunction "K_2") (pintype "passive"))
      (node (ref "R106") (pin "1") (pinfunction "1_1") (pintype "passive"))
    )
    (net (code "65") (name "Net-(LED12-A)") (class "Default")
      (node (ref "LED12") (pin "1") (pinfunction "A_1") (pintype "passive"))
      (node (ref "Q16") (pin "3") (pinfunction "C_3") (pintype "passive"))
    )
    (net (code "66") (name "Net-(LED12-K)") (class "Default")
      (node (ref "LED12") (pin "2") (pinfunction "K_2") (pintype "passive"))
      (node (ref "R114") (pin "1") (pinfunction "1_1") (pintype "passive"))
    )
    (net (code "67") (name "Net-(LED13-A)") (class "Default")
      (node (ref "LED13") (pin "1") (pinfunction "A_1") (pintype "passive"))
      (node (ref "Q19") (pin "3") (pinfunction "C_3") (pintype "passive"))
    )
    (net (code "68") (name "Net-(LED13-K)") (class "Default")
      (node (ref "LED13") (pin "2") (pinfunction "K_2") (pintype "passive"))
      (node (ref "R107") (pin "1") (pinfunction "1_1") (pintype "passive"))
    )
    (net (code "69") (name "Net-(LED14-A)") (class "Default")
      (node (ref "LED14") (pin "1") (pinfunction "A_1") (pintype "passive"))
      (node (ref "Q20") (pin "3") (pinfunction "C_3") (pintype "passive"))
    )
    (net (code "70") (name "Net-(LED14-K)") (class "Default")
      (node (ref "LED14") (pin "2") (pinfunction "K_2") (pintype "passive"))
      (node (ref "R115") (pin "1") (pinfunction "1_1") (pintype "passive"))
    )
    (net (code "71") (name "Net-(LED15-A)") (class "Default")
      (node (ref "LED15") (pin "1") (pinfunction "A_1") (pintype "passive"))
      (node (ref "Q21") (pin "3") (pinfunction "C_3") (pintype "passive"))
    )
    (net (code "72") (name "Net-(LED15-K)") (class "Default")
      (node (ref "LED15") (pin "2") (pinfunction "K_2") (pintype "passive"))
      (node (ref "R117") (pin "1") (pinfunction "1_1") (pintype "passive"))
    )
    (net (code "73") (name "Net-(LED16-A)") (class "Default")
      (node (ref "LED16") (pin "1") (pinfunction "A_1") (pintype "passive"))
      (node (ref "Q22") (pin "3") (pinfunction "C_3") (pintype "passive"))
    )
    (net (code "74") (name "Net-(LED16-K)") (class "Default")
      (node (ref "LED16") (pin "2") (pinfunction "K_2") (pintype "passive"))
      (node (ref "R108") (pin "1") (pinfunction "1_1") (pintype "passive"))
    )
    (net (code "75") (name "Net-(LED17-A)") (class "Default")
      (node (ref "LED17") (pin "1") (pinfunction "A_1") (pintype "passive"))
      (node (ref "Q23") (pin "3") (pinfunction "C_3") (pintype "passive"))
    )
    (net (code "76") (name "Net-(LED17-K)") (class "Default")
      (node (ref "LED17") (pin "2") (pinfunction "K_2") (pintype "passive"))
      (node (ref "R116") (pin "1") (pinfunction "1_1") (pintype "passive"))
    )
    (net (code "77") (name "Net-(LED18-A)") (class "Default")
      (node (ref "LED18") (pin "1") (pinfunction "A_1") (pintype "passive"))
      (node (ref "Q24") (pin "3") (pinfunction "C_3") (pintype "passive"))
    )
    (net (code "78") (name "Net-(LED18-K)") (class "Default")
      (node (ref "LED18") (pin "2") (pinfunction "K_2") (pintype "passive"))
      (node (ref "R118") (pin "1") (pinfunction "1_1") (pintype "passive"))
    )
    (net (code "79") (name "Net-(OC1-Pad1)") (class "Default")
      (node (ref "OC1") (pin "1") (pintype "passive"))
      (node (ref "R5") (pin "2") (pinfunction "2_2") (pintype "passive"))
    )
    (net (code "80") (name "Net-(OC1-Pad3)") (class "Default")
      (node (ref "OC1") (pin "3") (pintype "passive"))
      (node (ref "R7") (pin "1") (pinfunction "1_1") (pintype "passive"))
    )
    (net (code "81") (name "Net-(OC2-Pad1)") (class "Default")
      (node (ref "OC2") (pin "1") (pintype "passive"))
      (node (ref "R6") (pin "2") (pinfunction "2_2") (pintype "passive"))
    )
    (net (code "82") (name "Net-(OC2-Pad3)") (class "Default")
      (node (ref "OC2") (pin "3") (pintype "passive"))
      (node (ref "R8") (pin "1") (pinfunction "1_1") (pintype "passive"))
    )
    (net (code "83") (name "Net-(OC3-Pad1)") (class "Default")
      (node (ref "OC3") (pin "1") (pintype "passive"))
      (node (ref "R17") (pin "2") (pinfunction "2_2") (pintype "passive"))
    )
    (net (code "84") (name "Net-(OC3-Pad3)") (class "Default")
      (node (ref "OC3") (pin "3") (pintype "passive"))
      (node (ref "R19") (pin "1") (pinfunction "1_1") (pintype "passive"))
    )
    (net (code "85") (name "Net-(OC4-Pad1)") (class "Default")
      (node (ref "OC4") (pin "1") (pintype "passive"))
      (node (ref "R18") (pin "2") (pinfunction "2_2") (pintype "passive"))
    )
    (net (code "86") (name "Net-(OC4-Pad3)") (class "Default")
      (node (ref "OC4") (pin "3") (pintype "passive"))
      (node (ref "R20") (pin "1") (pinfunction "1_1") (pintype "passive"))
    )
    (net (code "87") (name "Net-(OC5-Pad1)") (class "Default")
      (node (ref "OC5") (pin "1") (pintype "passive"))
      (node (ref "R29") (pin "2") (pinfunction "2_2") (pintype "passive"))
    )
    (net (code "88") (name "Net-(OC5-Pad3)") (class "Default")
      (node (ref "OC5") (pin "3") (pintype "passive"))
      (node (ref "R33") (pin "1") (pinfunction "1_1") (pintype "passive"))
    )
    (net (code "89") (name "Net-(OC6-Pad1)") (class "Default")
      (node (ref "OC6") (pin "1") (pintype "passive"))
      (node (ref "R30") (pin "2") (pinfunction "2_2") (pintype "passive"))
    )
    (net (code "90") (name "Net-(OC6-Pad3)") (class "Default")
      (node (ref "OC6") (pin "3") (pintype "passive"))
      (node (ref "R34") (pin "1") (pinfunction "1_1") (pintype "passive"))
    )
    (net (code "91") (name "Net-(OC7-Pad1)") (class "Default")
      (node (ref "OC7") (pin "1") (pintype "passive"))
      (node (ref "R45") (pin "2") (pinfunction "2_2") (pintype "passive"))
    )
    (net (code "92") (name "Net-(OC7-Pad3)") (class "Default")
      (node (ref "OC7") (pin "3") (pintype "passive"))
      (node (ref "R48") (pin "1") (pinfunction "1_1") (pintype "passive"))
    )
    (net (code "93") (name "Net-(OC8-Pad1)") (class "Default")
      (node (ref "OC8") (pin "1") (pintype "passive"))
      (node (ref "R46") (pin "2") (pinfunction "2_2") (pintype "passive"))
    )
    (net (code "94") (name "Net-(OC8-Pad3)") (class "Default")
      (node (ref "OC8") (pin "3") (pintype "passive"))
      (node (ref "R49") (pin "1") (pinfunction "1_1") (pintype "passive"))
    )
    (net (code "95") (name "Net-(Q1-B)") (class "Default")
      (node (ref "Q1") (pin "1") (pinfunction "B_1") (pintype "passive"))
      (node (ref "R3") (pin "2") (pinfunction "2_2") (pintype "passive"))
    )
    (net (code "96") (name "Net-(Q2-B)") (class "Default")
      (node (ref "Q2") (pin "1") (pinfunction "B_1") (pintype "passive"))
      (node (ref "R4") (pin "2") (pinfunction "2_2") (pintype "passive"))
    )
    (net (code "97") (name "Net-(Q3-B)") (class "Default")
      (node (ref "Q3") (pin "2") (pinfunction "B_2") (pintype "passive"))
      (node (ref "R11") (pin "2") (pinfunction "2_2") (pintype "passive"))
      (node (ref "R7") (pin "2") (pinfunction "2_2") (pintype "passive"))
    )
    (net (code "98") (name "Net-(Q4-B)") (class "Default")
      (node (ref "Q4") (pin "2") (pinfunction "B_2") (pintype "passive"))
      (node (ref "R12") (pin "2") (pinfunction "2_2") (pintype "passive"))
      (node (ref "R8") (pin "2") (pinfunction "2_2") (pintype "passive"))
    )
    (net (code "99") (name "Net-(Q5-B)") (class "Default")
      (node (ref "Q5") (pin "1") (pinfunction "B_1") (pintype "passive"))
      (node (ref "R9") (pin "2") (pinfunction "2_2") (pintype "passive"))
    )
    (net (code "100") (name "Net-(Q6-B)") (class "Default")
      (node (ref "Q6") (pin "1") (pinfunction "B_1") (pintype "passive"))
      (node (ref "R10") (pin "2") (pinfunction "2_2") (pintype "passive"))
    )
    (net (code "101") (name "Net-(Q7-B)") (class "Default")
      (node (ref "Q7") (pin "1") (pinfunction "B_1") (pintype "passive"))
      (node (ref "R13") (pin "2") (pinfunction "2_2") (pintype "passive"))
    )
    (net (code "102") (name "Net-(Q8-B)") (class "Default")
      (node (ref "Q8") (pin "1") (pinfunction "B_1") (pintype "passive"))
      (node (ref "R14") (pin "2") (pinfunction "2_2") (pintype "passive"))
    )
    (net (code "103") (name "Net-(Q9-B)") (class "Default")
      (node (ref "Q9") (pin "2") (pinfunction "B_2") (pintype "passive"))
      (node (ref "R19") (pin "2") (pinfunction "2_2") (pintype "passive"))
      (node (ref "R23") (pin "2") (pinfunction "2_2") (pintype "passive"))
    )
    (net (code "104") (name "Net-(Q10-B)") (class "Default")
      (node (ref "Q10") (pin "2") (pinfunction "B_2") (pintype "passive"))
      (node (ref "R20") (pin "2") (pinfunction "2_2") (pintype "passive"))
      (node (ref "R24") (pin "2") (pinfunction "2_2") (pintype "passive"))
    )
    (net (code "105") (name "Net-(Q11-B)") (class "Default")
      (node (ref "Q11") (pin "1") (pinfunction "B_1") (pintype "passive"))
      (node (ref "R21") (pin "2") (pinfunction "2_2") (pintype "passive"))
    )
    (net (code "106") (name "Net-(Q12-B)") (class "Default")
      (node (ref "Q12") (pin "1") (pinfunction "B_1") (pintype "passive"))
      (node (ref "R22") (pin "2") (pinfunction "2_2") (pintype "passive"))
    )
    (net (code "107") (name "Net-(Q13-B)") (class "Default")
      (node (ref "Q13") (pin "1") (pinfunction "B_1") (pintype "passive"))
      (node (ref "R25") (pin "2") (pinfunction "2_2") (pintype "passive"))
    )
    (net (code "108") (name "Net-(Q14-B)") (class "Default")
      (node (ref "Q14") (pin "1") (pinfunction "B_1") (pintype "passive"))
      (node (ref "R26") (pin "2") (pinfunction "2_2") (pintype "passive"))
    )
    (net (code "109") (name "Net-(Q15-B)") (class "Default")
      (node (ref "Q15") (pin "1") (pinfunction "B_1") (pintype "passive"))
      (node (ref "R31") (pin "2") (pinfunction "2_2") (pintype "passive"))
    )
    (net (code "110") (name "Net-(Q16-B)") (class "Default")
      (node (ref "Q16") (pin "1") (pinfunction "B_1") (pintype "passive"))
      (node (ref "R32") (pin "2") (pinfunction "2_2") (pintype "passive"))
    )
    (net (code "111") (name "Net-(Q17-B)") (class "Default")
      (node (ref "Q17") (pin "2") (pinfunction "B_2") (pintype "passive"))
      (node (ref "R33") (pin "2") (pinfunction "2_2") (pintype "passive"))
      (node (ref "R35") (pin "2") (pinfunction "2_2") (pintype "passive"))
    )
    (net (code "112") (name "Net-(Q18-B)") (class "Default")
      (node (ref "Q18") (pin "2") (pinfunction "B_2") (pintype "passive"))
      (node (ref "R34") (pin "2") (pinfunction "2_2") (pintype "passive"))
      (node (ref "R36") (pin "2") (pinfunction "2_2") (pintype "passive"))
    )
    (net (code "113") (name "Net-(Q19-B)") (class "Default")
      (node (ref "Q19") (pin "1") (pinfunction "B_1") (pintype "passive"))
      (node (ref "R37") (pin "2") (pinfunction "2_2") (pintype "passive"))
    )
    (net (code "114") (name "Net-(Q20-B)") (class "Default")
      (node (ref "Q20") (pin "1") (pinfunction "B_1") (pintype "passive"))
      (node (ref "R38") (pin "2") (pinfunction "2_2") (pintype "passive"))
    )
    (net (code "115") (name "Net-(Q21-B)") (class "Default")
      (node (ref "Q21") (pin "1") (pinfunction "B_1") (pintype "passive"))
      (node (ref "R39") (pin "2") (pinfunction "2_2") (pintype "passive"))
    )
    (net (code "116") (name "Net-(Q22-B)") (class "Default")
      (node (ref "Q22") (pin "1") (pinfunction "B_1") (pintype "passive"))
      (node (ref "R43") (pin "2") (pinfunction "2_2") (pintype "passive"))
    )
    (net (code "117") (name "Net-(Q23-B)") (class "Default")
      (node (ref "Q23") (pin "1") (pinfunction "B_1") (pintype "passive"))
      (node (ref "R44") (pin "2") (pinfunction "2_2") (pintype "passive"))
    )
    (net (code "118") (name "Net-(Q24-B)") (class "Default")
      (node (ref "Q24") (pin "1") (pinfunction "B_1") (pintype "passive"))
      (node (ref "R47") (pin "2") (pinfunction "2_2") (pintype "passive"))
    )
    (net (code "119") (name "Net-(Q25-B)") (class "Default")
      (node (ref "Q25") (pin "2") (pinfunction "B_2") (pintype "passive"))
      (node (ref "R48") (pin "2") (pinfunction "2_2") (pintype "passive"))
      (node (ref "R50") (pin "2") (pinfunction "2_2") (pintype "passive"))
    )
    (net (code "120") (name "Net-(Q26-B)") (class "Default")
      (node (ref "Q26") (pin "2") (pinfunction "B_2") (pintype "passive"))
      (node (ref "R49") (pin "2") (pinfunction "2_2") (pintype "passive"))
      (node (ref "R51") (pin "2") (pinfunction "2_2") (pintype "passive"))
    )
    (net (code "121") (name "Net-(Q30-B)") (class "Default")
      (node (ref "Q30") (pin "1") (pinfunction "B_1") (pintype "passive"))
      (node (ref "R120") (pin "2") (pinfunction "2_2") (pintype "passive"))
    )
  )
)
